# Salida.net
KiCad netlist of a schematic drawn in Altium Designer
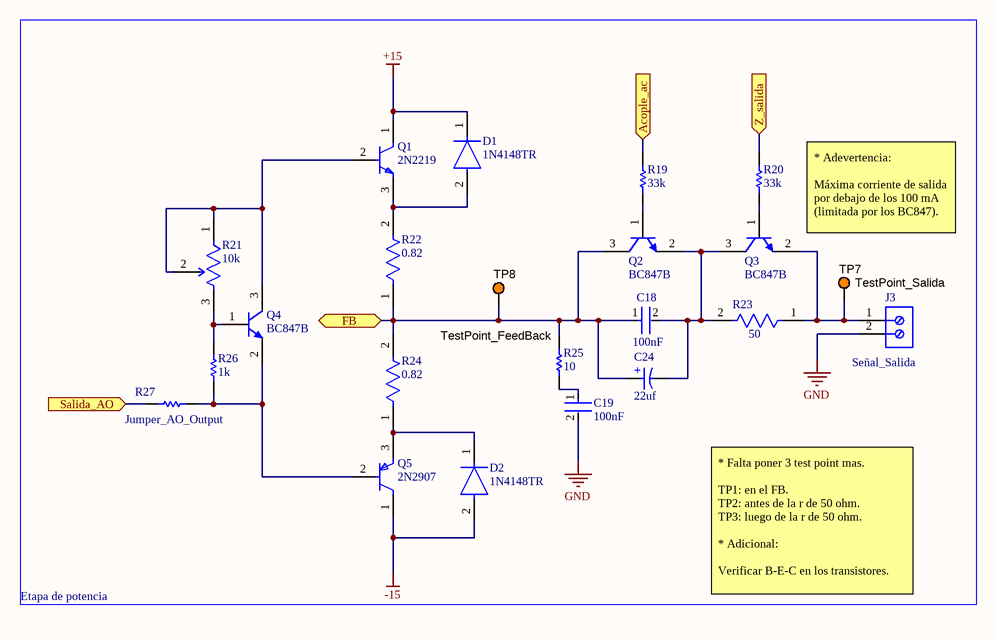
[diagram p0: Salida.SchDoc]

(export (version "E")
  (design (tool "Eeschema 10.0.6"))
  (components
    (comp (ref "C18")
      (value "100nF")
      (footprint "FP-0805-L_2_01_0_2-W_1_25-IPC_B")
      (description "General Purpose Ceramic Capacitor, 0805, 100nF, 10%, X7R, 15%, 100V")
      (fields (field (name "VOLTAGE") "100V") (field (name "TOLERANCE") "10%"))
      (libsource (lib "Altium Content Vault") (part "b4654b650e69147ec39a6b967a45e02"))
    )
    (comp (ref "C19")
      (value "100nF")
      (footprint "FP-0805-L_2_01_0_2-W_1_25-IPC_B")
      (description "General Purpose Ceramic Capacitor, 0805, 100nF, 10%, X7R, 15%, 100V")
      (fields (field (name "VOLTAGE") "100V") (field (name "TOLERANCE") "10%"))
      (libsource (lib "Altium Content Vault") (part "b4654b650e69147ec39a6b967a45e02"))
    )
    (comp (ref "C24")
      (value "22uf")
      (footprint "WCAP-ASLU_D4H5.5")
      (description "865090640004 WCAP-ASLU Aluminum Electrolytic Capacitors")
      (fields (field (name "TOLERANCE") "20%"))
      (libsource (lib "Altium Content Vault") (part "Capacitor_Polarized"))
    )
    (comp (ref "D1")
      (value "1N4148TR")
      (footprint "FP-6_560-5004_12-4-MFG")
      (description "DIODE GEN PURP 75V 300MA DO35")
      (libsource (lib "Altium Content Vault") (part "d7152d700b627762746794eb795d46e"))
    )
    (comp (ref "D2")
      (value "1N4148TR")
      (footprint "FP-6_560-5004_12-4-MFG")
      (description "DIODE GEN PURP 75V 300MA DO35")
      (libsource (lib "Altium Content Vault") (part "d7152d700b627762746794eb795d46e"))
    )
    (comp (ref "J3")
      (value "Señal_Salida")
      (footprint "691102710002")
      (fields (field (name "VOLTAGE") "300V"))
      (libsource (lib "Altium Content Vault") (part "TBL - 1R - 02P - Screw"))
    )
    (comp (ref "Q1")
      (value "2N2219")
      (footprint "FP-135AR-MFG")
      (description "BC548CTA Small Signal Bipolar Transistor, 0.1A I(C), 30V V(BR)CEO, 1-Element, NPN, Silicon, TO-92")
      (libsource (lib "Altium Content Vault") (part "ddb5dc480c9317d3b8a15cf6cf16fd3"))
    )
    (comp (ref "Q2")
      (value "BC847B")
      (footprint "INF-SOT23_L")
      (description "NPN Silicon AF Transistor, 45 V VCEO, 100 mA IC, SOT23, Reel, Green")
      (fields (field (name "MANUFACTURER") "Infineon"))
      (libsource (lib "Altium Content Vault") (part "INF-BJTNPN-BEC-3"))
    )
    (comp (ref "Q3")
      (value "BC847B")
      (footprint "INF-SOT23_L")
      (description "NPN Silicon AF Transistor, 45 V VCEO, 100 mA IC, SOT23, Reel, Green")
      (fields (field (name "MANUFACTURER") "Infineon"))
      (libsource (lib "Altium Content Vault") (part "INF-BJTNPN-BEC-3"))
    )
    (comp (ref "Q4")
      (value "BC847B")
      (footprint "INF-SOT23_L")
      (description "NPN Silicon AF Transistor, 45 V VCEO, 100 mA IC, SOT23, Reel, Green")
      (fields (field (name "MANUFACTURER") "Infineon"))
      (libsource (lib "Altium Content Vault") (part "INF-BJTNPN-BEC-3"))
    )
    (comp (ref "Q5")
      (value "2N2907")
      (footprint "FP-135AR-MFG")
      (description "BC557BTF Small Signal Bipolar Transistor, 0.1A I(C), 45V V(BR)CEO, 1-Element, PNP, Silicon, TO-92")
      (libsource (lib "Altium Content Vault") (part "9e2844d3eb996af6824d2c99fe21afc"))
    )
    (comp (ref "R19")
      (value "33k")
      (footprint "RESC2013X60X35ML10T20")
      (description "Chip Resistor, 1 KOhm, +/- 1%, 125 mW, -55 to 155 degC, 0805 (2012 Metric), RoHS, Tape and Reel")
      (fields (field (name "TOLERANCE") "1%") (field (name "MANUFACTURER") "Yageo"))
      (libsource (lib "Altium Content Vault") (part "RES-2"))
    )
    (comp (ref "R20")
      (value "33k")
      (footprint "RESC2013X60X35ML10T20")
      (description "Chip Resistor, 1 KOhm, +/- 1%, 125 mW, -55 to 155 degC, 0805 (2012 Metric), RoHS, Tape and Reel")
      (fields (field (name "TOLERANCE") "1%") (field (name "MANUFACTURER") "Yageo"))
      (libsource (lib "Altium Content Vault") (part "RES-2"))
    )
    (comp (ref "R21")
      (value "10k")
      (footprint "FP-3296W-MFG")
      (description "TRIMMER 500 OHM 0.5W PC PIN TOP")
      (fields (field (name "TOLERANCE") "10%"))
      (libsource (lib "Altium Content Vault") (part "2dcfd2547301a7d3209a5e99acfd772"))
    )
    (comp (ref "R22")
      (value "0.82")
      (footprint "FP-RLR07-MFG")
      (fields (field (name "TOLERANCE") "1%"))
      (libsource (lib "Altium Content Vault") (part "1029c3af85768c4190bb7ad29bc67b5"))
    )
    (comp (ref "R23")
      (value "50")
      (footprint "FP-RLR07-MFG")
      (fields (field (name "TOLERANCE") "1%"))
      (libsource (lib "Altium Content Vault") (part "1029c3af85768c4190bb7ad29bc67b5"))
    )
    (comp (ref "R24")
      (value "0.82")
      (footprint "FP-RLR07-MFG")
      (fields (field (name "TOLERANCE") "1%"))
      (libsource (lib "Altium Content Vault") (part "1029c3af85768c4190bb7ad29bc67b5"))
    )
    (comp (ref "R25")
      (value "10")
      (footprint "RESC2013X60X35ML10T20")
      (description "Chip Resistor, 1 KOhm, +/- 1%, 125 mW, -55 to 155 degC, 0805 (2012 Metric), RoHS, Tape and Reel")
      (fields (field (name "TOLERANCE") "1%") (field (name "MANUFACTURER") "Yageo"))
      (libsource (lib "Altium Content Vault") (part "RES-2"))
    )
    (comp (ref "R26")
      (value "1k")
      (footprint "RESC2013X60X35ML10T20")
      (description "Chip Resistor, 1 KOhm, +/- 1%, 125 mW, -55 to 155 degC, 0805 (2012 Metric), RoHS, Tape and Reel")
      (fields (field (name "TOLERANCE") "1%") (field (name "MANUFACTURER") "Yageo"))
      (libsource (lib "Altium Content Vault") (part "RES-2"))
    )
    (comp (ref "R27")
      (value "Jumper_AO_Output")
      (footprint "RESC2013X50X30LL20T20")
      (fields (field (name "MANUFACTURER") "Vishay Dale") (field (name "PART NUMBER") "CRCW08050000Z0EA"))
      (libsource (lib "Altium Content Vault") (part "RES"))
    )
    (comp (ref "TP7")
      (value "TestPoint_Salida")
      (footprint "KSTN-5003")
      (description "Test Point, Orange, 1-Pin THD, RoHS")
      (libsource (lib "Altium Content Vault") (part "TESTPOINT_ORANGE"))
    )
    (comp (ref "TP8")
      (value "TestPoint_FeedBack")
      (footprint "KSTN-5003")
      (description "Test Point, Orange, 1-Pin THD, RoHS")
      (libsource (lib "Altium Content Vault") (part "TESTPOINT_ORANGE"))
    )
  )
  (nets
    (net (code "1") (name "+15") (class "Default")
      (node (ref "D1") (pin "1") (pinfunction "C_1") (pintype "passive"))
      (node (ref "Q1") (pin "1") (pinfunction "C_1") (pintype "passive"))
    )
    (net (code "2") (name "-15") (class "Default")
      (node (ref "D2") (pin "2") (pinfunction "A_2") (pintype "passive"))
      (node (ref "Q5") (pin "1") (pinfunction "C_1") (pintype "passive"))
    )
    (net (code "3") (name "/Acople_ac") (class "Default")
      (node (ref "R19") (pin "2") (pinfunction "2_2") (pintype "passive"))
    )
    (net (code "4") (name "/FB") (class "Default")
      (node (ref "C18") (pin "1") (pinfunction "1_1") (pintype "passive"))
      (node (ref "C24") (pin "1") (pinfunction "P_1") (pintype "passive"))
      (node (ref "Q2") (pin "3") (pinfunction "C_3") (pintype "passive"))
      (node (ref "R22") (pin "1") (pinfunction "1_1") (pintype "passive"))
      (node (ref "R24") (pin "2") (pinfunction "2_2") (pintype "passive"))
      (node (ref "R25") (pin "2") (pinfunction "2_2") (pintype "passive"))
      (node (ref "TP8") (pin "1") (pinfunction "1_1") (pintype "passive"))
    )
    (net (code "5") (name "/Salida_AO") (class "Default")
      (node (ref "R27") (pin "1") (pinfunction "1_1") (pintype "passive"))
    )
    (net (code "6") (name "/Z_salida") (class "Default")
      (node (ref "R20") (pin "2") (pinfunction "2_2") (pintype "passive"))
    )
    (net (code "7") (name "GND") (class "Default")
      (node (ref "C19") (pin "2") (pinfunction "2_2") (pintype "passive"))
      (node (ref "J3") (pin "2") (pinfunction "2_2") (pintype "passive"))
    )
    (net (code "8") (name "Net-(C19-Pad1)") (class "Default")
      (node (ref "C19") (pin "1") (pinfunction "1_1") (pintype "passive"))
      (node (ref "R25") (pin "1") (pinfunction "1_1") (pintype "passive"))
    )
    (net (code "9") (name "Net-(C24-N)") (class "Default")
      (node (ref "C18") (pin "2") (pinfunction "2_2") (pintype "passive"))
      (node (ref "C24") (pin "2") (pinfunction "N_2") (pintype "passive"))
      (node (ref "Q2") (pin "2") (pinfunction "E_2") (pintype "passive"))
      (node (ref "Q3") (pin "3") (pinfunction "C_3") (pintype "passive"))
      (node (ref "R23") (pin "2") (pinfunction "2_2") (pintype "passive"))
    )
    (net (code "10") (name "Net-(D1-A)") (class "Default")
      (node (ref "D1") (pin "2") (pinfunction "A_2") (pintype "passive"))
      (node (ref "Q1") (pin "3") (pinfunction "E_3") (pintype "passive"))
      (node (ref "R22") (pin "2") (pinfunction "2_2") (pintype "passive"))
    )
    (net (code "11") (name "Net-(D2-C)") (class "Default")
      (node (ref "D2") (pin "1") (pinfunction "C_1") (pintype "passive"))
      (node (ref "Q5") (pin "3") (pinfunction "E_3") (pintype "passive"))
      (node (ref "R24") (pin "1") (pinfunction "1_1") (pintype "passive"))
    )
    (net (code "12") (name "Net-(Q1-B)") (class "Default")
      (node (ref "Q1") (pin "2") (pinfunction "B_2") (pintype "passive"))
      (node (ref "Q4") (pin "3") (pinfunction "C_3") (pintype "passive"))
      (node (ref "R21") (pin "1") (pinfunction "CCW_1") (pintype "passive"))
      (node (ref "R21") (pin "2") (pinfunction "WIPER_2") (pintype "passive"))
    )
    (net (code "13") (name "Net-(Q2-B)") (class "Default")
      (node (ref "Q2") (pin "1") (pinfunction "B_1") (pintype "passive"))
      (node (ref "R19") (pin "1") (pinfunction "1_1") (pintype "passive"))
    )
    (net (code "14") (name "Net-(Q3-B)") (class "Default")
      (node (ref "Q3") (pin "1") (pinfunction "B_1") (pintype "passive"))
      (node (ref "R20") (pin "1") (pinfunction "1_1") (pintype "passive"))
    )
    (net (code "15") (name "Net-(Q3-E)") (class "Default")
      (node (ref "J3") (pin "1") (pinfunction "1_1") (pintype "passive"))
      (node (ref "Q3") (pin "2") (pinfunction "E_2") (pintype "passive"))
      (node (ref "R23") (pin "1") (pinfunction "1_1") (pintype "passive"))
      (node (ref "TP7") (pin "1") (pinfunction "1_1") (pintype "passive"))
    )
    (net (code "16") (name "Net-(Q4-B)") (class "Default")
      (node (ref "Q4") (pin "1") (pinfunction "B_1") (pintype "passive"))
      (node (ref "R21") (pin "3") (pinfunction "CW_3") (pintype "passive"))
      (node (ref "R26") (pin "2") (pinfunction "2_2") (pintype "passive"))
    )
    (net (code "17") (name "Net-(Q4-E)") (class "Default")
      (node (ref "Q4") (pin "2") (pinfunction "E_2") (pintype "passive"))
      (node (ref "Q5") (pin "2") (pinfunction "B_2") (pintype "passive"))
      (node (ref "R26") (pin "1") (pinfunction "1_1") (pintype "passive"))
      (node (ref "R27") (pin "2") (pinfunction "2_2") (pintype "passive"))
    )
  )
)
